# H0FR1.net
KiCad netlist of a schematic drawn in EAGLE
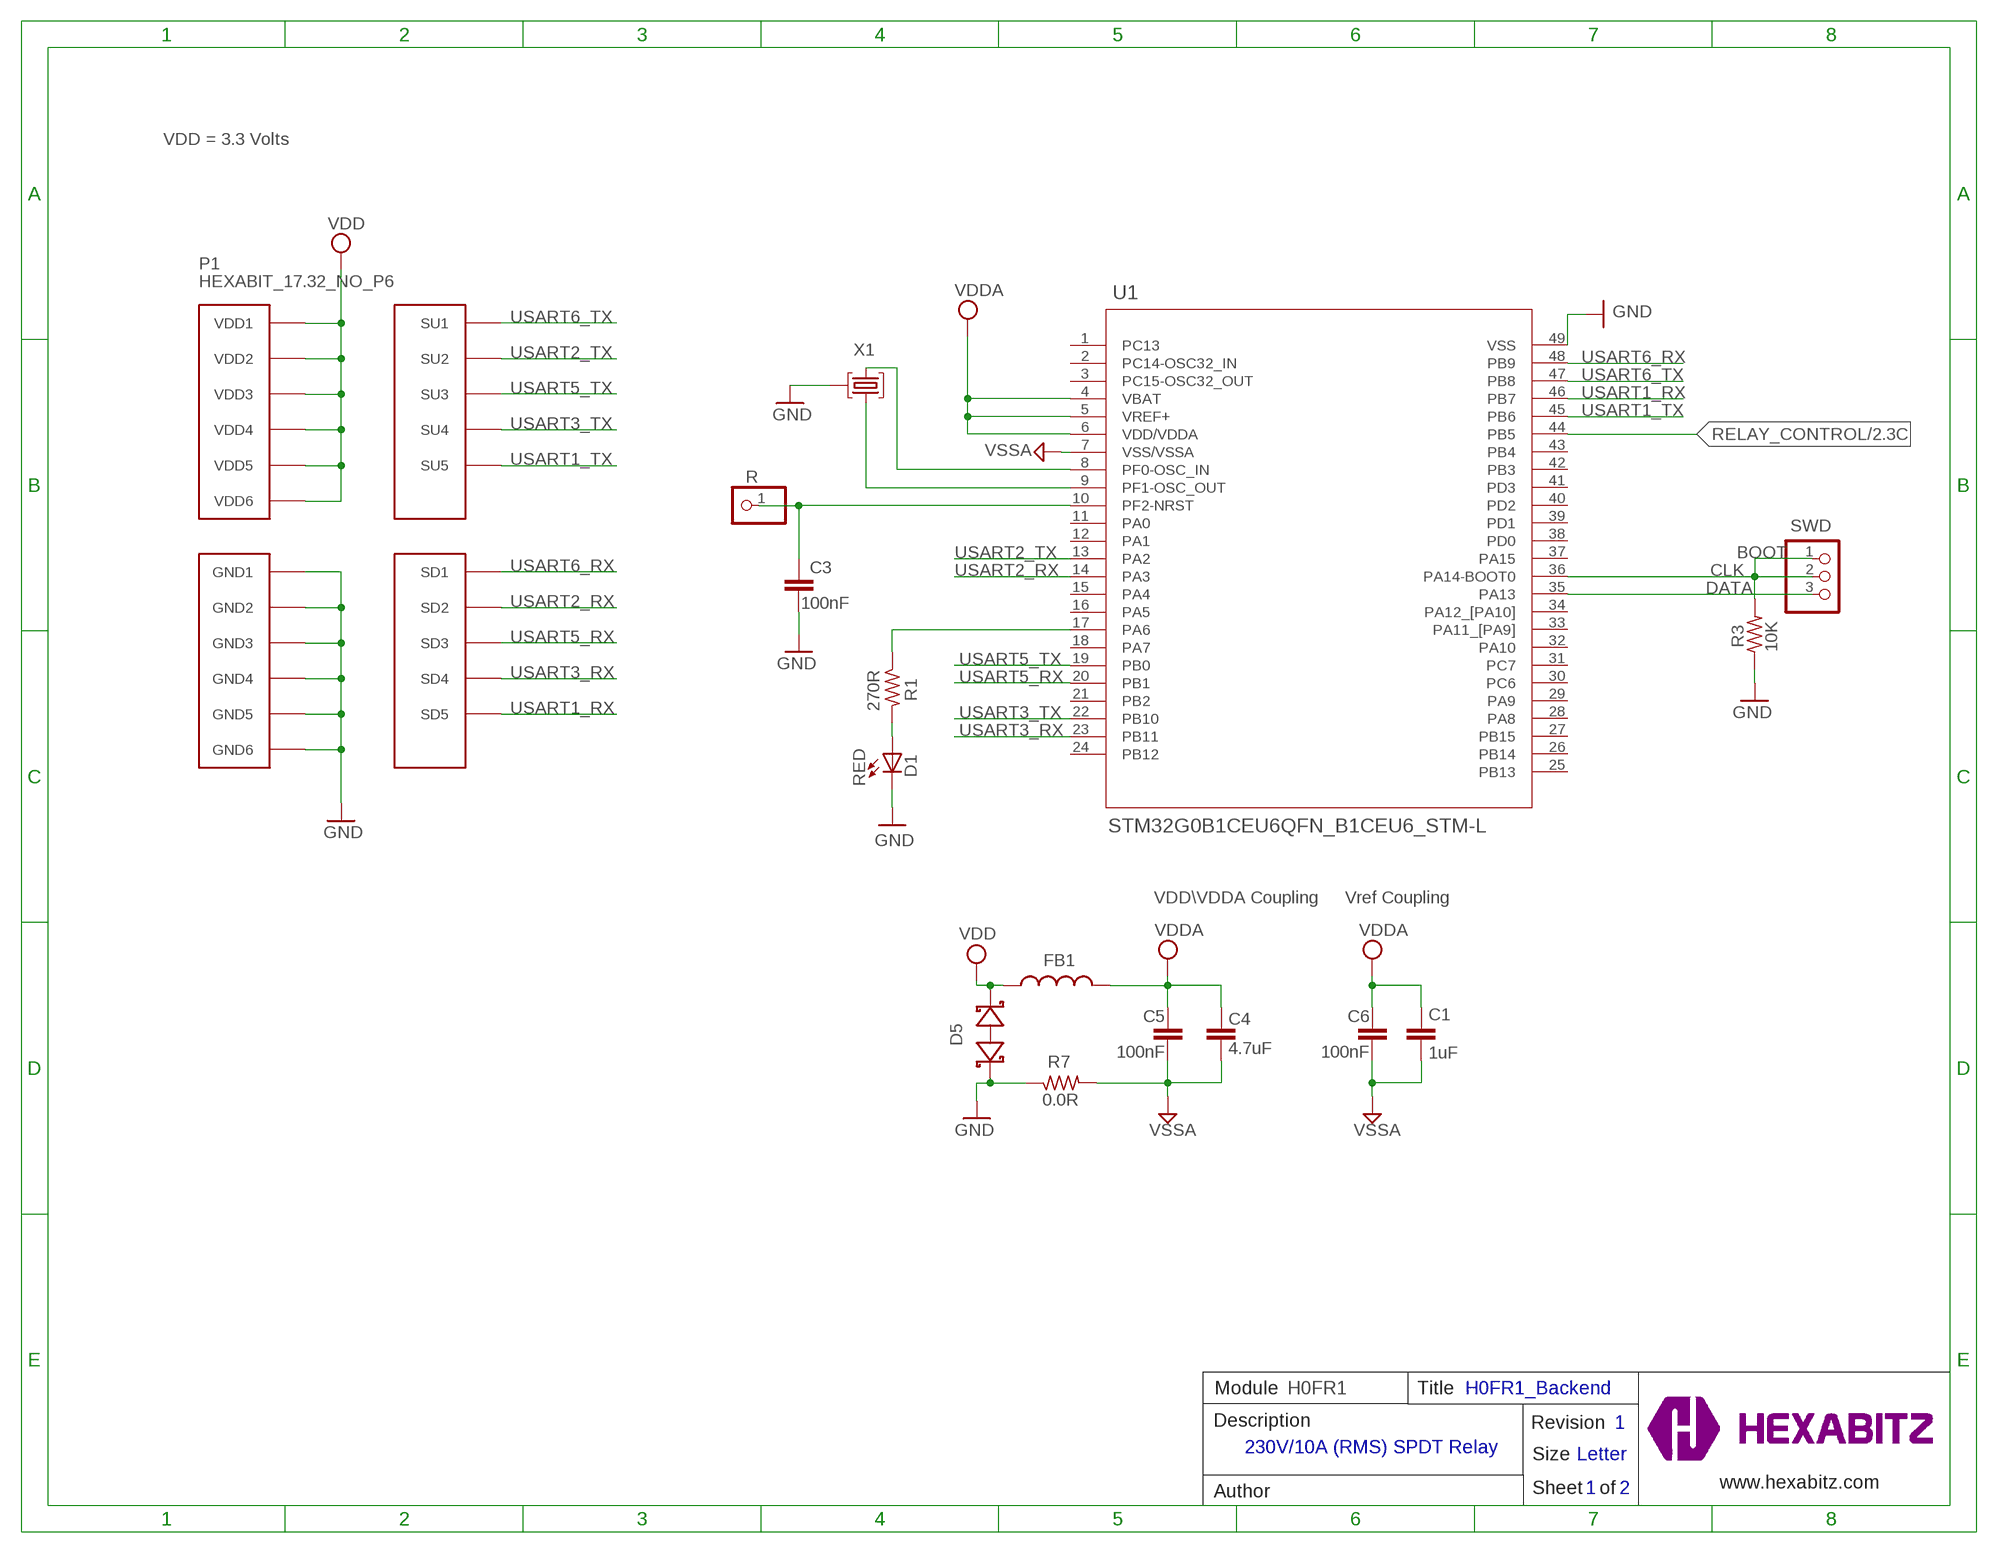
[diagram p0: schematic, sheet 1]
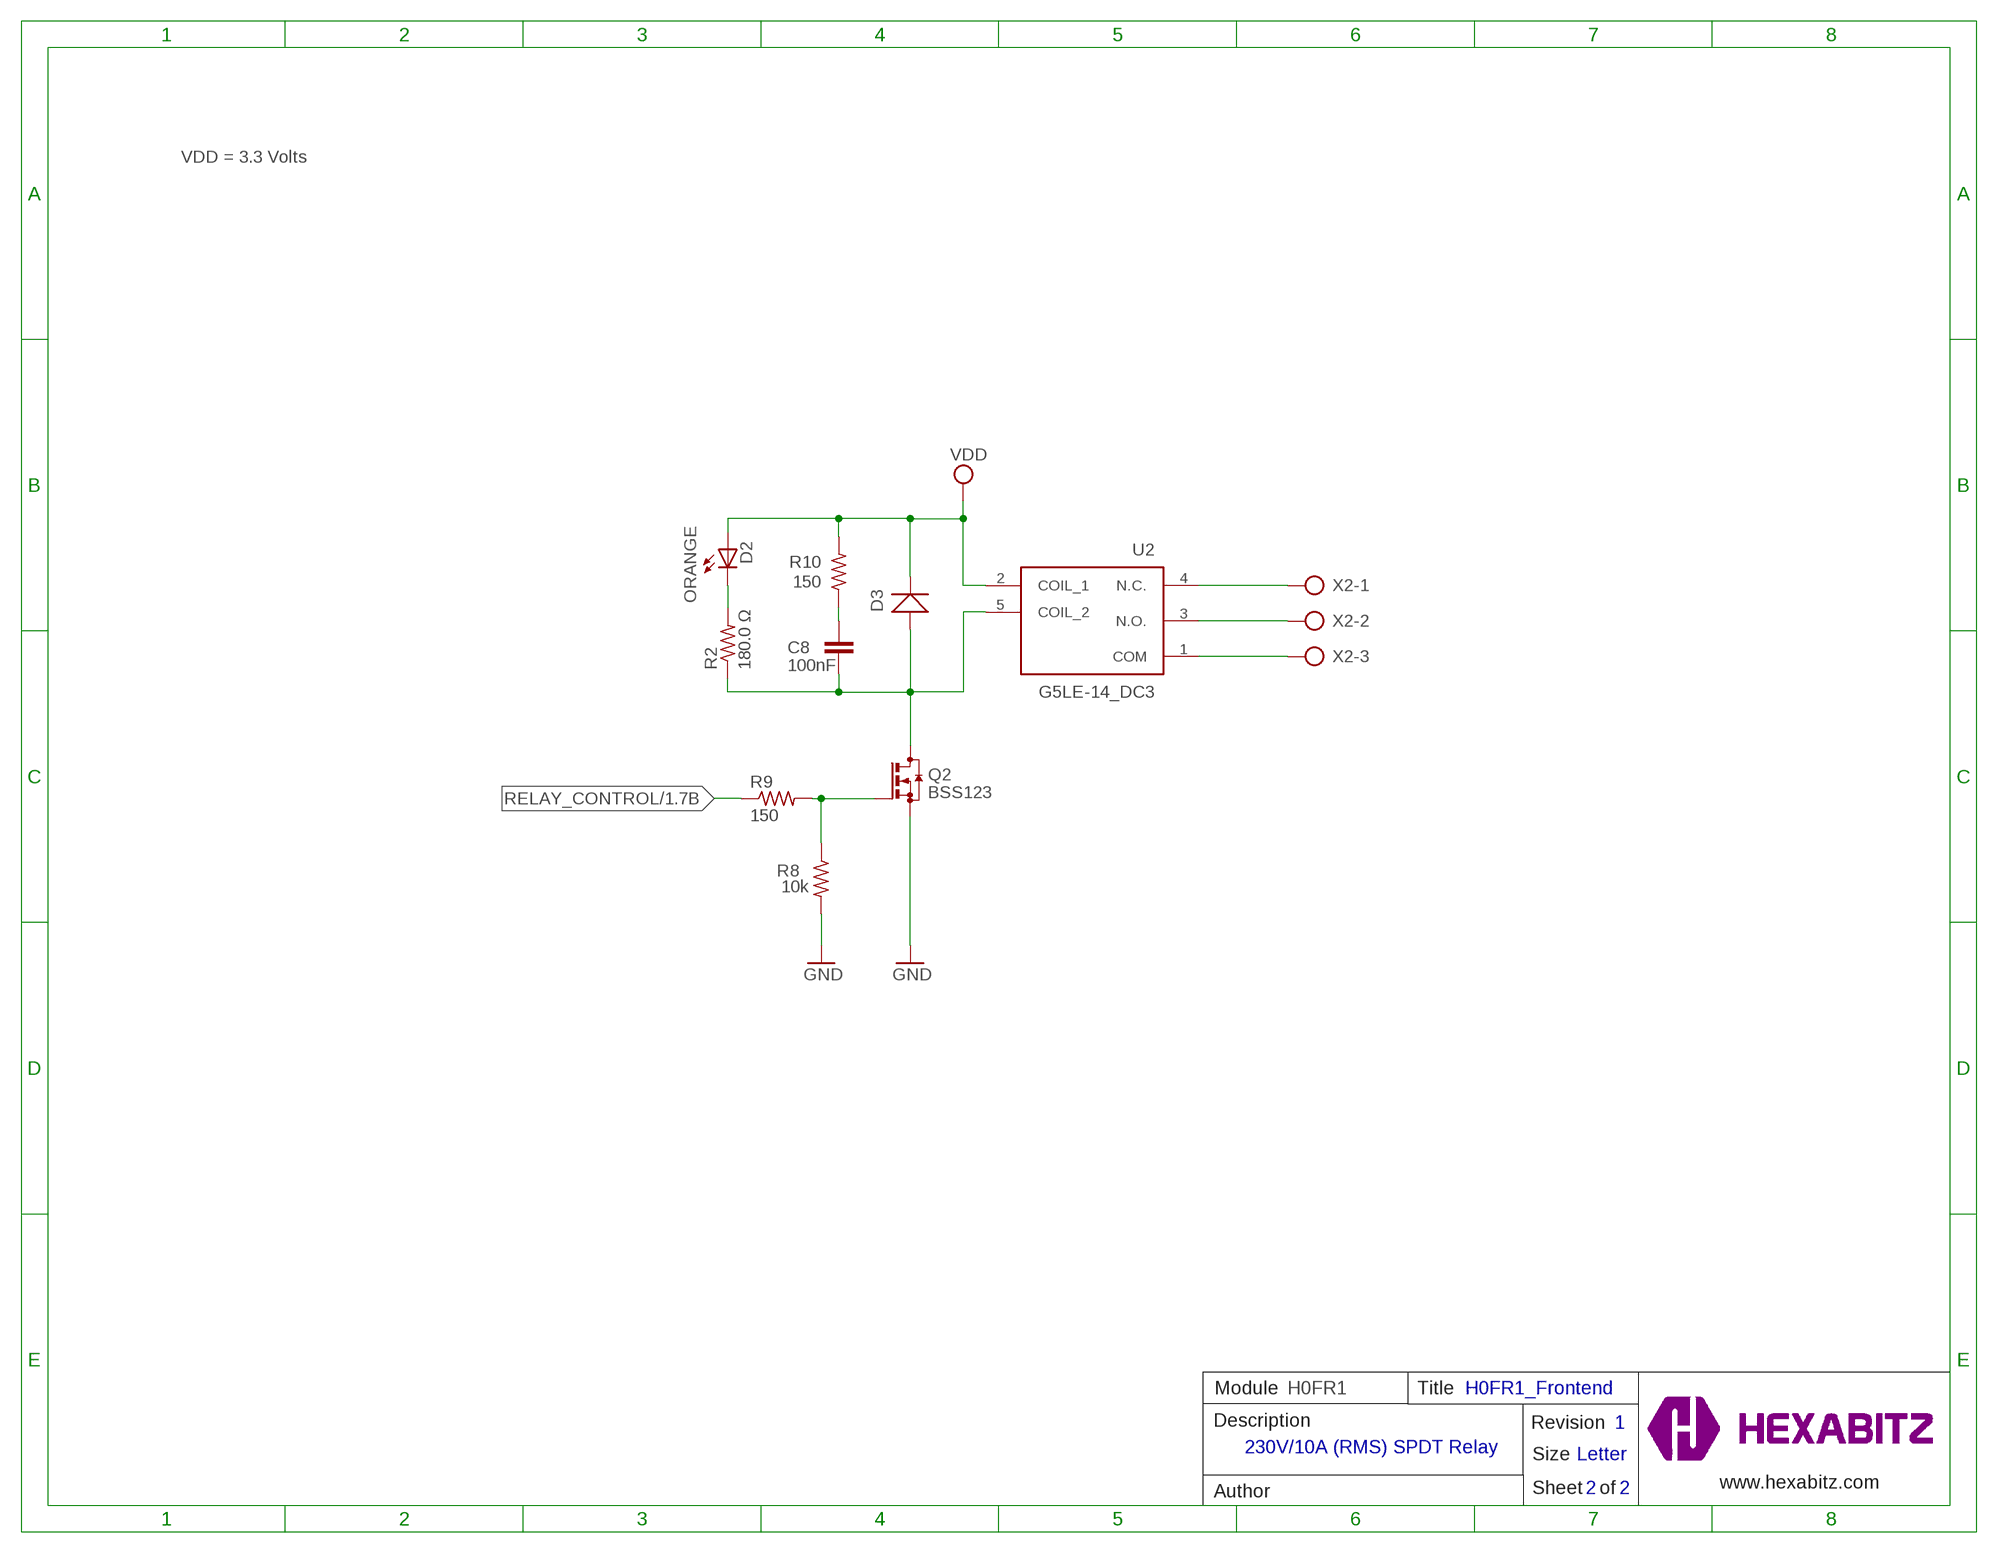
[diagram p1: schematic, sheet 2]

(export (version "E")
  (design (tool "Eeschema 10.0.6"))
  (components
    (comp (ref "C1")
      (value "1uF")
      (footprint "eagle-import:C-0805")
      (libsource (lib "eagle-import") (part "C-0805"))
    )
    (comp (ref "C3")
      (value "100nF")
      (footprint "eagle-import:C-0603")
      (libsource (lib "eagle-import") (part "C-0603"))
    )
    (comp (ref "C4")
      (value "4.7uF")
      (footprint "eagle-import:C-0805")
      (libsource (lib "eagle-import") (part "C-0805"))
    )
    (comp (ref "C5")
      (value "100nF")
      (footprint "eagle-import:C-0603")
      (libsource (lib "eagle-import") (part "C-0603"))
    )
    (comp (ref "C6")
      (value "100nF")
      (footprint "eagle-import:C-0603")
      (libsource (lib "eagle-import") (part "C-0603"))
    )
    (comp (ref "D1")
      (value "RED")
      (footprint "eagle-import:VLMS1300-GS08")
      (fields
        (field (name "MPN") "VLMS1300-GS08")
        (field (name "MFN") "Vishay")
        (field (name "MPN_1") "VLMS1300-GS08")
        (field (name "OCTOPART_URL") "https://octopart.com/vlms1300-gs08-vishay-21709201?r=sp&s=_gcP4_q8T1SC6PJQPTQ9yA")
      )
      (libsource (lib "eagle-import") (part "VLMS1300-GS08"))
    )
    (comp (ref "D5")
      (value "BOURNS_CDSOD323-T03SCBOURNS_CDSOD323-T03SC_0_0")
      (footprint "eagle-import:BOURNS_CDSOD323-T03SC_0")
      (fields (field (name "MPN") "CDSOD323-T03SC"))
      (libsource (lib "eagle-import") (part "BOURNS_CDSOD323-T03SCBOURNS_CDSOD323-T03SC_0_0"))
    )
    (comp (ref "FB1")
      (value "FB-TDK_MMZ1608Y300B")
      (footprint "eagle-import:FB-0603")
      (fields
        (field (name "MFN") "TDK ")
        (field (name "MPN") "MMZ1608Y300B")
        (field (name "OCTOPART_URL") "https://octopart.com/mmz1608y300b-tdk-368280?r=sp&s=cd9_2ZEqQ9q9UNBuQgHAiA")
      )
      (libsource (lib "eagle-import") (part "FB-0603"))
    )
    (comp (ref "P1")
      (value "HEXABIT_17.32_NO_P6")
      (footprint "eagle-import:HEXABIT_17.32_NO_P6")
      (libsource (lib "eagle-import") (part "HEXABIT_?_NO_P617.32"))
    )
    (comp (ref "R")
      (value "R")
      (footprint "eagle-import:1X01")
      (fields (field (name "MPN") "87227-1"))
      (libsource (lib "eagle-import") (part "PINHD-1X1"))
    )
    (comp (ref "R1")
      (value "270R")
      (footprint "eagle-import:R-0603")
      (libsource (lib "eagle-import") (part "R-0603"))
    )
    (comp (ref "R3")
      (value "10K")
      (footprint "eagle-import:R-0603")
      (libsource (lib "eagle-import") (part "R-0603"))
    )
    (comp (ref "R7")
      (value "0.0R")
      (footprint "eagle-import:R-0603")
      (fields
        (field (name "MFN") "Yageo")
        (field (name "MPN") "RC0603JR-070RL")
        (field (name "OCTOPART_URL") "https://octopart.com/rc0603jr-070rl-yageo-1241539?r=sp&s=X2NteqRjRNWrnx42Y0aliA")
        (field (name "RESISTANCE") "0.0 Ohm")
      )
      (libsource (lib "eagle-import") (part "R-0603"))
    )
    (comp (ref "SWD")
      (value "PINHD-1X3")
      (footprint "eagle-import:1X03")
      (libsource (lib "eagle-import") (part "PINHD-1X3"))
    )
    (comp (ref "TRIMBLE-LOGO1")
      (value "HEXA-LOGO")
      (footprint "eagle-import:HEXA-LOGO")
      (libsource (lib "eagle-import") (part "HEXA-LOGO"))
    )
    (comp (ref "U1")
      (value "STM32G0B1CEU6QFN_B1CEU6_STM-L")
      (footprint "eagle-import:QFN_B1CEU6_STM-L")
      (fields
        (field (name "MANUFACTURER_PART_NUMBER") "STM32G0B1CEU6")
        (field (name "SPICEPREFIX") "X")
        (field (name "COPYRIGHT") "Copyright (C) 2021 Ultra Librarian. All rights reserved.")
      )
      (libsource (lib "eagle-import") (part "STM32G0B1CEU6QFN_B1CEU6_STM-L"))
    )
    (comp (ref "X1")
      (value "XTALL_CSTCE8M00G52")
      (footprint "eagle-import:XTALL_CSTCE8M00G52")
      (fields (field (name "MPN") "CSTCE8M00G52Z-R0"))
      (libsource (lib "eagle-import") (part "XTALL_CSTCE8M00G52"))
    )
    (comp (ref "C8")
      (value "100nF")
      (footprint "eagle-import:C-0603")
      (fields
        (field (name "CAPACITANCE") "100nF")
        (field (name "MFN") "KEMET")
        (field (name "MPN") "C0603C104K8RACTU")
        (field (name "OCTOPART_URL") "https://octopart.com/c0603c104k8ractu-kemet-145075?r=sp&s=9bS9ASSwSEqMCE9KBEQZ0g")
        (field (name "TOLERANCE") "10%")
        (field (name "VOLTAGE_RATING") "10V")
      )
      (libsource (lib "eagle-import") (part "C-0603"))
    )
    (comp (ref "D2")
      (value "orange")
      (footprint "eagle-import:VLMS1300-GS08")
      (fields
        (field (name "MPN") "VLMS1300-GS08")
        (field (name "COULOR") "ORANGE")
        (field (name "MFN") "Vishay ")
        (field (name "MPN_1") "VLMY1300-GS08")
        (field (name "OCTOPART_URL") "https://octopart.com/vlmy1300-gs08-vishay-21709204")
      )
      (libsource (lib "eagle-import") (part "Hexabitz_VLMS1300-GS08"))
    )
    (comp (ref "D3")
      (value "40V 300MA")
      (footprint "eagle-import:SOD-323")
      (fields (field (name "MPN") "BAT54JFILM"))
      (libsource (lib "eagle-import") (part "BAT54JFILM_SOD-323"))
    )
    (comp (ref "Q2")
      (value "BSS123")
      (footprint "eagle-import:SOT23")
      (libsource (lib "eagle-import") (part "BSS123"))
    )
    (comp (ref "R2")
      (value "180.0 Ω")
      (footprint "eagle-import:R-0603")
      (fields
        (field (name "MFN") "Panasonic")
        (field (name "MPN") "ERJ-3GEYJ181V")
        (field (name "OCTOPART_URL") "https://octopart.com/erj-3geyj181v-panasonic-55403673")
        (field (name "RESISTANCE") "180.0 Ω")
        (field (name "TOLERANCE") "±5%")
      )
      (libsource (lib "eagle-import") (part "R-0603"))
    )
    (comp (ref "R8")
      (value "10k")
      (footprint "eagle-import:R-0603")
      (fields
        (field (name "MFN") "Yageo")
        (field (name "MPN") "RC0603JR-07680KL")
        (field (name "OCTOPART_URL") "https://octopart.com/rc0603jr-07680kl-yageo-40953169?r=sp")
        (field (name "RESISTANCE") "680K Ohm")
        (field (name "TOLERANCE") "5%")
      )
      (libsource (lib "eagle-import") (part "R-0603"))
    )
    (comp (ref "R9")
      (value "150")
      (footprint "eagle-import:R-0603")
      (fields
        (field (name "MFN") "Vishay")
        (field (name "MPN") "CRCW06031K00JNEA")
        (field (name "OCTOPART_URL") "https://octopart.com/crcw06031k00jnea-vishay-55388219?r=sp")
        (field (name "RESISTANCE") "1000.0 Ω")
        (field (name "TOLERANCE") "±5%")
      )
      (libsource (lib "eagle-import") (part "R-0603"))
    )
    (comp (ref "R10")
      (value "150")
      (footprint "eagle-import:R-0603")
      (fields
        (field (name "MFN") "Yageo")
        (field (name "MPN") "RC0603JR-07680KL")
        (field (name "OCTOPART_URL") "https://octopart.com/rc0603jr-07680kl-yageo-40953169?r=sp")
        (field (name "RESISTANCE") "680K Ohm")
        (field (name "TOLERANCE") "5%")
      )
      (libsource (lib "eagle-import") (part "R-0603"))
    )
    (comp (ref "U2")
      (value "G5LE-14_DC3")
      (footprint "eagle-import:G5LE-14_SPDT")
      (fields
        (field (name "MANUFACTURER_PART_NUMBER") "G5LE-14 DC3")
        (field (name "MOUSER_PART_NUMBER") "653-G5LE-14DC3")
      )
      (libsource (lib "eagle-import") (part "G5LE-14_DC3"))
    )
    (comp (ref "X2")
      (value "AK300/3")
      (footprint "eagle-import:AK300_3")
      (libsource (lib "eagle-import") (part "AK300/3"))
    )
  )
  (nets
    (net (code "1") (name "CLK") (class "Default")
      (node (ref "R3") (pin "2") (pinfunction "2_2") (pintype "passive"))
      (node (ref "SWD") (pin "1") (pinfunction "1_1") (pintype "passive"))
      (node (ref "SWD") (pin "2") (pinfunction "2_2") (pintype "passive"))
      (node (ref "U1") (pin "36") (pinfunction "PA14-BOOT0_36") (pintype "bidirectional"))
    )
    (net (code "2") (name "DATA") (class "Default")
      (node (ref "SWD") (pin "3") (pinfunction "3_3") (pintype "passive"))
      (node (ref "U1") (pin "35") (pinfunction "PA13_35") (pintype "bidirectional"))
    )
    (net (code "3") (name "GND") (class "Default")
      (node (ref "C3") (pin "2") (pinfunction "2_2") (pintype "passive"))
      (node (ref "D1") (pin "C") (pinfunction "C_C") (pintype "passive"))
      (node (ref "D5") (pin "1") (pinfunction "A_1") (pintype "passive"))
      (node (ref "P1") (pin "PAD_PD10") (pinfunction "GND4_PAD_PD10") (pintype "power_in"))
      (node (ref "P1") (pin "PAD_PD11") (pinfunction "GND5_PAD_PD11") (pintype "power_in"))
      (node (ref "P1") (pin "PAD_PD12") (pinfunction "GND6_PAD_PD12") (pintype "power_in"))
      (node (ref "P1") (pin "PAD_PD7") (pinfunction "GND1_PAD_PD7") (pintype "power_in"))
      (node (ref "P1") (pin "PAD_PD8") (pinfunction "GND2_PAD_PD8") (pintype "power_in"))
      (node (ref "P1") (pin "PAD_PD9") (pinfunction "GND3_PAD_PD9") (pintype "power_in"))
      (node (ref "Q2") (pin "2") (pinfunction "S_2") (pintype "passive"))
      (node (ref "R3") (pin "1") (pinfunction "1_1") (pintype "passive"))
      (node (ref "R7") (pin "1") (pinfunction "1_1") (pintype "passive"))
      (node (ref "R8") (pin "2") (pinfunction "2_2") (pintype "passive"))
      (node (ref "U1") (pin "49") (pinfunction "VSS_49") (pintype "passive"))
      (node (ref "X1") (pin "P$2") (pinfunction "2_P$2") (pintype "passive"))
    )
    (net (code "4") (name "Net-(C8-Pad1)") (class "Default")
      (node (ref "C8") (pin "1") (pinfunction "1_1") (pintype "passive"))
      (node (ref "R10") (pin "1") (pinfunction "1_1") (pintype "passive"))
    )
    (net (code "5") (name "Net-(D1-PadA)") (class "Default")
      (node (ref "D1") (pin "A") (pinfunction "A_A") (pintype "passive"))
      (node (ref "R1") (pin "2") (pinfunction "2_2") (pintype "passive"))
    )
    (net (code "6") (name "Net-(D2-PadC)") (class "Default")
      (node (ref "D2") (pin "C") (pinfunction "C_C") (pintype "passive"))
      (node (ref "R2") (pin "2") (pinfunction "2_2") (pintype "passive"))
    )
    (net (code "7") (name "Net-(Q2-D)") (class "Default")
      (node (ref "C8") (pin "2") (pinfunction "2_2") (pintype "passive"))
      (node (ref "D3") (pin "+") (pinfunction "+_+") (pintype "passive"))
      (node (ref "Q2") (pin "3") (pinfunction "D_3") (pintype "passive"))
      (node (ref "R2") (pin "1") (pinfunction "1_1") (pintype "passive"))
      (node (ref "U2") (pin "5") (pinfunction "COIL_2_5") (pintype "bidirectional"))
    )
    (net (code "8") (name "Net-(Q2-G)") (class "Default")
      (node (ref "Q2") (pin "1") (pinfunction "G_1") (pintype "passive"))
      (node (ref "R8") (pin "1") (pinfunction "1_1") (pintype "passive"))
      (node (ref "R9") (pin "2") (pinfunction "2_2") (pintype "passive"))
    )
    (net (code "9") (name "Net-(U1-PA6)") (class "Default")
      (node (ref "R1") (pin "1") (pinfunction "1_1") (pintype "passive"))
      (node (ref "U1") (pin "17") (pinfunction "PA6_17") (pintype "bidirectional"))
    )
    (net (code "10") (name "Net-(U1-PF0-OSC_IN)") (class "Default")
      (node (ref "U1") (pin "8") (pinfunction "PF0-OSC_IN_8") (pintype "bidirectional"))
      (node (ref "X1") (pin "P$3") (pinfunction "3_P$3") (pintype "passive"))
    )
    (net (code "11") (name "Net-(U1-PF1-OSC_OUT)") (class "Default")
      (node (ref "U1") (pin "9") (pinfunction "PF1-OSC_OUT_9") (pintype "output"))
      (node (ref "X1") (pin "P$1") (pinfunction "1_P$1") (pintype "passive"))
    )
    (net (code "12") (name "Net-(U1-PF2-NRST)") (class "Default")
      (node (ref "C3") (pin "1") (pinfunction "1_1") (pintype "passive"))
      (node (ref "R") (pin "1") (pinfunction "1_1") (pintype "passive"))
      (node (ref "U1") (pin "10") (pinfunction "PF2-NRST_10") (pintype "bidirectional"))
    )
    (net (code "13") (name "Net-(U2-COM)") (class "Default")
      (node (ref "U2") (pin "1") (pinfunction "COM_1") (pintype "bidirectional"))
      (node (ref "X2") (pin "3") (pinfunction "KL_3") (pintype "passive"))
    )
    (net (code "14") (name "Net-(U2-N.C.)") (class "Default")
      (node (ref "U2") (pin "4") (pinfunction "N.C._4") (pintype "bidirectional"))
      (node (ref "X2") (pin "1") (pinfunction "KL_1") (pintype "passive"))
    )
    (net (code "15") (name "Net-(U2-N.O.)") (class "Default")
      (node (ref "U2") (pin "3") (pinfunction "N.O._3") (pintype "bidirectional"))
      (node (ref "X2") (pin "2") (pinfunction "KL_2") (pintype "passive"))
    )
    (net (code "16") (name "RELAY_CONTROL") (class "Default")
      (node (ref "R9") (pin "1") (pinfunction "1_1") (pintype "passive"))
      (node (ref "U1") (pin "44") (pinfunction "PB5_44") (pintype "bidirectional"))
    )
    (net (code "17") (name "USART1_RX") (class "Default")
      (node (ref "P1") (pin "PAD_PD5") (pinfunction "SD5_PAD_PD5") (pintype "bidirectional"))
      (node (ref "U1") (pin "46") (pinfunction "PB7_46") (pintype "bidirectional"))
    )
    (net (code "18") (name "USART1_TX") (class "Default")
      (node (ref "P1") (pin "PAD_PU5") (pinfunction "SU5_PAD_PU5") (pintype "bidirectional"))
      (node (ref "U1") (pin "45") (pinfunction "PB6_45") (pintype "bidirectional"))
    )
    (net (code "19") (name "USART2_RX") (class "Default")
      (node (ref "P1") (pin "PAD_PD2") (pinfunction "SD2_PAD_PD2") (pintype "bidirectional"))
      (node (ref "U1") (pin "14") (pinfunction "PA3_14") (pintype "bidirectional"))
    )
    (net (code "20") (name "USART2_TX") (class "Default")
      (node (ref "P1") (pin "PAD_PU2") (pinfunction "SU2_PAD_PU2") (pintype "bidirectional"))
      (node (ref "U1") (pin "13") (pinfunction "PA2_13") (pintype "bidirectional"))
    )
    (net (code "21") (name "USART3_RX") (class "Default")
      (node (ref "P1") (pin "PAD_PD4") (pinfunction "SD4_PAD_PD4") (pintype "bidirectional"))
      (node (ref "U1") (pin "23") (pinfunction "PB11_23") (pintype "bidirectional"))
    )
    (net (code "22") (name "USART3_TX") (class "Default")
      (node (ref "P1") (pin "PAD_PU4") (pinfunction "SU4_PAD_PU4") (pintype "bidirectional"))
      (node (ref "U1") (pin "22") (pinfunction "PB10_22") (pintype "bidirectional"))
    )
    (net (code "23") (name "USART5_RX") (class "Default")
      (node (ref "P1") (pin "PAD_PD3") (pinfunction "SD3_PAD_PD3") (pintype "bidirectional"))
      (node (ref "U1") (pin "20") (pinfunction "PB1_20") (pintype "bidirectional"))
    )
    (net (code "24") (name "USART5_TX") (class "Default")
      (node (ref "P1") (pin "PAD_PU3") (pinfunction "SU3_PAD_PU3") (pintype "bidirectional"))
      (node (ref "U1") (pin "19") (pinfunction "PB0_19") (pintype "bidirectional"))
    )
    (net (code "25") (name "USART6_RX") (class "Default")
      (node (ref "P1") (pin "PAD_PD1") (pinfunction "SD1_PAD_PD1") (pintype "bidirectional"))
      (node (ref "U1") (pin "48") (pinfunction "PB9_48") (pintype "bidirectional"))
    )
    (net (code "26") (name "USART6_TX") (class "Default")
      (node (ref "P1") (pin "PAD_PU1") (pinfunction "SU1_PAD_PU1") (pintype "bidirectional"))
      (node (ref "U1") (pin "47") (pinfunction "PB8_47") (pintype "bidirectional"))
    )
    (net (code "27") (name "VDD") (class "Default")
      (node (ref "D2") (pin "A") (pinfunction "A_A") (pintype "passive"))
      (node (ref "D3") (pin "-") (pinfunction "-_-") (pintype "passive"))
      (node (ref "D5") (pin "2") (pinfunction "C_2") (pintype "passive"))
      (node (ref "FB1") (pin "2") (pinfunction "2_2") (pintype "passive"))
      (node (ref "P1") (pin "PAD_PU10") (pinfunction "VDD4_PAD_PU10") (pintype "power_in"))
      (node (ref "P1") (pin "PAD_PU11") (pinfunction "VDD5_PAD_PU11") (pintype "power_in"))
      (node (ref "P1") (pin "PAD_PU12") (pinfunction "VDD6_PAD_PU12") (pintype "power_in"))
      (node (ref "P1") (pin "PAD_PU7") (pinfunction "VDD1_PAD_PU7") (pintype "power_in"))
      (node (ref "P1") (pin "PAD_PU8") (pinfunction "VDD2_PAD_PU8") (pintype "power_in"))
      (node (ref "P1") (pin "PAD_PU9") (pinfunction "VDD3_PAD_PU9") (pintype "power_in"))
      (node (ref "R10") (pin "2") (pinfunction "2_2") (pintype "passive"))
      (node (ref "U2") (pin "2") (pinfunction "COIL_1_2") (pintype "bidirectional"))
    )
    (net (code "28") (name "VDDA") (class "Default")
      (node (ref "C1") (pin "1") (pinfunction "1_1") (pintype "passive"))
      (node (ref "C4") (pin "1") (pinfunction "1_1") (pintype "passive"))
      (node (ref "C5") (pin "1") (pinfunction "1_1") (pintype "passive"))
      (node (ref "C6") (pin "1") (pinfunction "1_1") (pintype "passive"))
      (node (ref "FB1") (pin "1") (pinfunction "1_1") (pintype "passive"))
      (node (ref "U1") (pin "4") (pinfunction "VBAT_4") (pintype "passive"))
      (node (ref "U1") (pin "5") (pinfunction "VREF+_5") (pintype "power_in"))
      (node (ref "U1") (pin "6") (pinfunction "VDD/VDDA_6") (pintype "power_in"))
    )
    (net (code "29") (name "VSSA") (class "Default")
      (node (ref "C1") (pin "2") (pinfunction "2_2") (pintype "passive"))
      (node (ref "C4") (pin "2") (pinfunction "2_2") (pintype "passive"))
      (node (ref "C5") (pin "2") (pinfunction "2_2") (pintype "passive"))
      (node (ref "C6") (pin "2") (pinfunction "2_2") (pintype "passive"))
      (node (ref "R7") (pin "2") (pinfunction "2_2") (pintype "passive"))
      (node (ref "U1") (pin "7") (pinfunction "VSS/VSSA_7") (pintype "passive"))
    )
    (net (code "30") (name "unconnected-(U1-PA0-Pad11)") (class "Default")
      (node (ref "U1") (pin "11") (pinfunction "PA0_11") (pintype "bidirectional"))
    )
    (net (code "31") (name "unconnected-(U1-PA1-Pad12)") (class "Default")
      (node (ref "U1") (pin "12") (pinfunction "PA1_12") (pintype "bidirectional"))
    )
    (net (code "32") (name "unconnected-(U1-PA4-Pad15)") (class "Default")
      (node (ref "U1") (pin "15") (pinfunction "PA4_15") (pintype "bidirectional"))
    )
    (net (code "33") (name "unconnected-(U1-PA5-Pad16)") (class "Default")
      (node (ref "U1") (pin "16") (pinfunction "PA5_16") (pintype "bidirectional"))
    )
    (net (code "34") (name "unconnected-(U1-PA7-Pad18)") (class "Default")
      (node (ref "U1") (pin "18") (pinfunction "PA7_18") (pintype "bidirectional"))
    )
    (net (code "35") (name "unconnected-(U1-PA8-Pad28)") (class "Default")
      (node (ref "U1") (pin "28") (pinfunction "PA8_28") (pintype "bidirectional"))
    )
    (net (code "36") (name "unconnected-(U1-PA9-Pad29)") (class "Default")
      (node (ref "U1") (pin "29") (pinfunction "PA9_29") (pintype "bidirectional"))
    )
    (net (code "37") (name "unconnected-(U1-PA10-Pad32)") (class "Default")
      (node (ref "U1") (pin "32") (pinfunction "PA10_32") (pintype "bidirectional"))
    )
    (net (code "38") (name "unconnected-(U1-PA11_[PA9]-Pad33)") (class "Default")
      (node (ref "U1") (pin "33") (pinfunction "PA11_[PA9]_33") (pintype "bidirectional"))
    )
    (net (code "39") (name "unconnected-(U1-PA12_[PA10]-Pad34)") (class "Default")
      (node (ref "U1") (pin "34") (pinfunction "PA12_[PA10]_34") (pintype "bidirectional"))
    )
    (net (code "40") (name "unconnected-(U1-PA15-Pad37)") (class "Default")
      (node (ref "U1") (pin "37") (pinfunction "PA15_37") (pintype "bidirectional"))
    )
    (net (code "41") (name "unconnected-(U1-PB2-Pad21)") (class "Default")
      (node (ref "U1") (pin "21") (pinfunction "PB2_21") (pintype "bidirectional"))
    )
    (net (code "42") (name "unconnected-(U1-PB3-Pad42)") (class "Default")
      (node (ref "U1") (pin "42") (pinfunction "PB3_42") (pintype "bidirectional"))
    )
    (net (code "43") (name "unconnected-(U1-PB4-Pad43)") (class "Default")
      (node (ref "U1") (pin "43") (pinfunction "PB4_43") (pintype "bidirectional"))
    )
    (net (code "44") (name "unconnected-(U1-PB12-Pad24)") (class "Default")
      (node (ref "U1") (pin "24") (pinfunction "PB12_24") (pintype "bidirectional"))
    )
    (net (code "45") (name "unconnected-(U1-PB13-Pad25)") (class "Default")
      (node (ref "U1") (pin "25") (pinfunction "PB13_25") (pintype "bidirectional"))
    )
    (net (code "46") (name "unconnected-(U1-PB14-Pad26)") (class "Default")
      (node (ref "U1") (pin "26") (pinfunction "PB14_26") (pintype "bidirectional"))
    )
    (net (code "47") (name "unconnected-(U1-PB15-Pad27)") (class "Default")
      (node (ref "U1") (pin "27") (pinfunction "PB15_27") (pintype "bidirectional"))
    )
    (net (code "48") (name "unconnected-(U1-PC6-Pad30)") (class "Default")
      (node (ref "U1") (pin "30") (pinfunction "PC6_30") (pintype "bidirectional"))
    )
    (net (code "49") (name "unconnected-(U1-PC7-Pad31)") (class "Default")
      (node (ref "U1") (pin "31") (pinfunction "PC7_31") (pintype "bidirectional"))
    )
    (net (code "50") (name "unconnected-(U1-PC13-Pad1)") (class "Default")
      (node (ref "U1") (pin "1") (pinfunction "PC13_1") (pintype "bidirectional"))
    )
    (net (code "51") (name "unconnected-(U1-PC14-OSC32_IN-Pad2)") (class "Default")
      (node (ref "U1") (pin "2") (pinfunction "PC14-OSC32_IN_2") (pintype "bidirectional"))
    )
    (net (code "52") (name "unconnected-(U1-PC15-OSC32_OUT-Pad3)") (class "Default")
      (node (ref "U1") (pin "3") (pinfunction "PC15-OSC32_OUT_3") (pintype "output"))
    )
    (net (code "53") (name "unconnected-(U1-PD0-Pad38)") (class "Default")
      (node (ref "U1") (pin "38") (pinfunction "PD0_38") (pintype "bidirectional"))
    )
    (net (code "54") (name "unconnected-(U1-PD1-Pad39)") (class "Default")
      (node (ref "U1") (pin "39") (pinfunction "PD1_39") (pintype "bidirectional"))
    )
    (net (code "55") (name "unconnected-(U1-PD2-Pad40)") (class "Default")
      (node (ref "U1") (pin "40") (pinfunction "PD2_40") (pintype "bidirectional"))
    )
    (net (code "56") (name "unconnected-(U1-PD3-Pad41)") (class "Default")
      (node (ref "U1") (pin "41") (pinfunction "PD3_41") (pintype "bidirectional"))
    )
  )
)
